# Alimentation.net
KiCad netlist of a schematic drawn in EAGLE
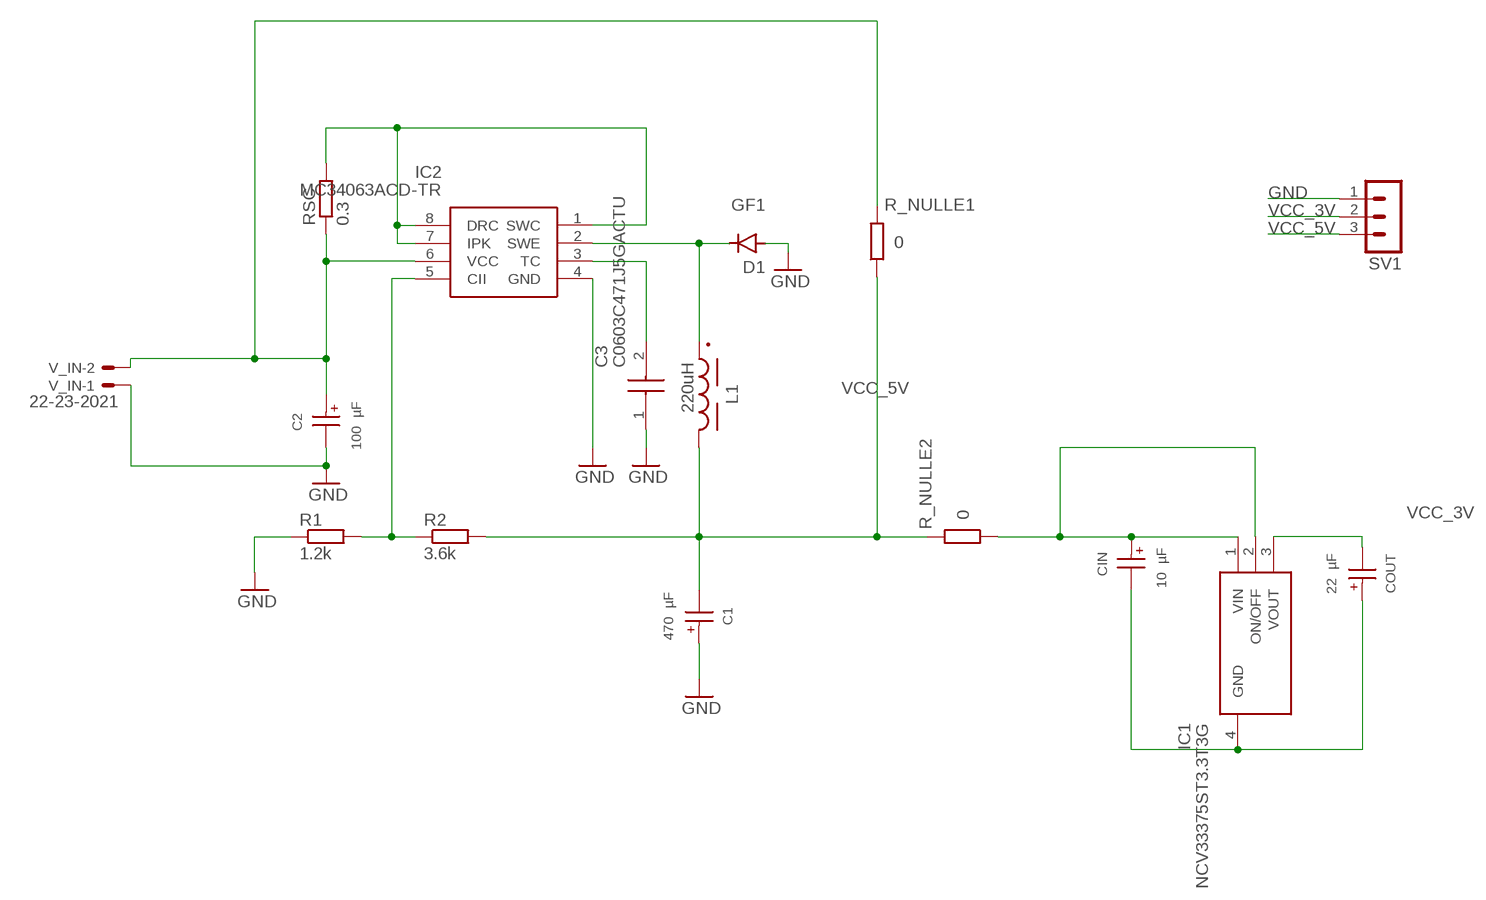
[diagram p0: schematic, sheet 1]

(export (version "E")
  (design (tool "Eeschema 10.0.6"))
  (components
    (comp (ref "C1")
      (value "470 µF")
      (footprint "eagle-import:WCAP-ASLL_8X10.5(DXL)")
      (libsource (lib "eagle-import") (part "WCAP-ASLL_8X10.5_865060353009"))
    )
    (comp (ref "C2")
      (value "100 µF")
      (footprint "eagle-import:WCAP-ASLL_6.3X7.7(DXL)")
      (libsource (lib "eagle-import") (part "WCAP-ASLL_6.3X7.7_865060445005"))
    )
    (comp (ref "C3")
      (value "C0603C471J5GACTU")
      (footprint "eagle-import:C0603")
      (fields (field (name "MOUSER_PART_NUMBER") "80-C0603C471J5G"))
      (libsource (lib "eagle-import") (part "C0603C471J5GACTU"))
    )
    (comp (ref "CIN")
      (value "10 µF")
      (footprint "eagle-import:WCAP-ASLL_4X5.5(DXL)")
      (libsource (lib "eagle-import") (part "WCAP-ASLL_4X5.5_865060440001"))
    )
    (comp (ref "COUT")
      (value "22 µF")
      (footprint "eagle-import:WCAP-ASLL_5X5.5(DXL)")
      (libsource (lib "eagle-import") (part "WCAP-ASLL_5X5.5_865060442002"))
    )
    (comp (ref "D1")
      (value "GF1")
      (footprint "eagle-import:SMA-DO214AC")
      (libsource (lib "eagle-import") (part "GF1"))
    )
    (comp (ref "IC1")
      (value "NCV33375ST3.3T3G")
      (footprint "eagle-import:SOT230P700X175-4N")
      (fields (field (name "MOUSER_PART_NUMBER") "863-NCV33375ST3.3T3G"))
      (libsource (lib "eagle-import") (part "NCV33375ST3.3T3G"))
    )
    (comp (ref "IC2")
      (value "MC34063ACD-TR")
      (footprint "eagle-import:SOIC127P600X175-8N")
      (fields (field (name "MOUSER_PART_NUMBER") "511-MC34063ACD-TR"))
      (libsource (lib "eagle-import") (part "MC34063ACD-TR"))
    )
    (comp (ref "L1")
      (value "220uH")
      (footprint "eagle-import:WE-PDA_1260")
      (libsource (lib "eagle-import") (part "WE-PDA_1260_784771221"))
    )
    (comp (ref "R1")
      (value "1.2k")
      (footprint "eagle-import:R0603")
      (libsource (lib "eagle-import") (part "R-EU_R0603"))
    )
    (comp (ref "R2")
      (value "3.6k")
      (footprint "eagle-import:R0603")
      (libsource (lib "eagle-import") (part "R-EU_R0603"))
    )
    (comp (ref "RSC")
      (value "0.3")
      (footprint "eagle-import:R1206W")
      (libsource (lib "eagle-import") (part "R-EU_R1206W"))
    )
    (comp (ref "R_NULLE1")
      (value "0")
      (footprint "eagle-import:R0603")
      (libsource (lib "eagle-import") (part "R-EU_R0603"))
    )
    (comp (ref "R_NULLE2")
      (value "0")
      (footprint "eagle-import:R0603")
      (libsource (lib "eagle-import") (part "R-EU_R0603"))
    )
    (comp (ref "SV1")
      (value "MA03-1")
      (footprint "eagle-import:MA03-1")
      (libsource (lib "eagle-import") (part "MA03-1"))
    )
    (comp (ref "V_IN")
      (value "22-23-2021")
      (footprint "eagle-import:22-23-2021")
      (fields (field (name "MF") "MOLEX"))
      (libsource (lib "eagle-import") (part "22-23-2021"))
    )
  )
  (nets
    (net (code "1") (name "/VCC_3V") (class "Default")
      (node (ref "COUT") (pin "2") (pinfunction "-_2") (pintype "passive"))
      (node (ref "IC1") (pin "3") (pinfunction "VOUT_3") (pintype "bidirectional"))
      (node (ref "SV1") (pin "2") (pinfunction "2_2") (pintype "passive"))
    )
    (net (code "2") (name "/VCC_5V") (class "Default")
      (node (ref "C1") (pin "2") (pinfunction "-_2") (pintype "passive"))
      (node (ref "L1") (pin "2") (pinfunction "2_2") (pintype "passive"))
      (node (ref "R2") (pin "2") (pinfunction "2_2") (pintype "passive"))
      (node (ref "R_NULLE1") (pin "1") (pinfunction "1_1") (pintype "passive"))
      (node (ref "R_NULLE2") (pin "2") (pinfunction "2_2") (pintype "passive"))
      (node (ref "SV1") (pin "3") (pinfunction "3_3") (pintype "passive"))
    )
    (net (code "3") (name "GND") (class "Default")
      (node (ref "C1") (pin "1") (pinfunction "+_1") (pintype "passive"))
      (node (ref "C2") (pin "2") (pinfunction "-_2") (pintype "passive"))
      (node (ref "C3") (pin "1") (pinfunction "1_1") (pintype "bidirectional"))
      (node (ref "CIN") (pin "2") (pinfunction "-_2") (pintype "passive"))
      (node (ref "COUT") (pin "1") (pinfunction "+_1") (pintype "passive"))
      (node (ref "D1") (pin "A") (pinfunction "A_A") (pintype "passive"))
      (node (ref "IC1") (pin "4") (pinfunction "GND_4") (pintype "bidirectional"))
      (node (ref "IC2") (pin "4") (pinfunction "GND_4") (pintype "bidirectional"))
      (node (ref "R1") (pin "1") (pinfunction "1_1") (pintype "passive"))
      (node (ref "SV1") (pin "1") (pinfunction "1_1") (pintype "passive"))
      (node (ref "V_IN") (pin "1") (pinfunction "S_1") (pintype "passive"))
    )
    (net (code "4") (name "Net-(C2-+)") (class "Default")
      (node (ref "C2") (pin "1") (pinfunction "+_1") (pintype "passive"))
      (node (ref "IC2") (pin "6") (pinfunction "VCC_6") (pintype "bidirectional"))
      (node (ref "RSC") (pin "1") (pinfunction "1_1") (pintype "passive"))
      (node (ref "R_NULLE1") (pin "2") (pinfunction "2_2") (pintype "passive"))
      (node (ref "V_IN") (pin "2") (pinfunction "S_2") (pintype "passive"))
    )
    (net (code "5") (name "Net-(CIN-+)") (class "Default")
      (node (ref "CIN") (pin "1") (pinfunction "+_1") (pintype "passive"))
      (node (ref "IC1") (pin "1") (pinfunction "VIN_1") (pintype "bidirectional"))
      (node (ref "IC1") (pin "2") (pinfunction "ON/OFF_2") (pintype "bidirectional"))
      (node (ref "R_NULLE2") (pin "1") (pinfunction "1_1") (pintype "passive"))
    )
    (net (code "6") (name "Net-(D1-C)") (class "Default")
      (node (ref "D1") (pin "K") (pinfunction "C_K") (pintype "passive"))
      (node (ref "IC2") (pin "2") (pinfunction "SWE_2") (pintype "bidirectional"))
      (node (ref "L1") (pin "1") (pinfunction "1_1") (pintype "passive"))
    )
    (net (code "7") (name "Net-(IC2-CII)") (class "Default")
      (node (ref "IC2") (pin "5") (pinfunction "CII_5") (pintype "bidirectional"))
      (node (ref "R1") (pin "2") (pinfunction "2_2") (pintype "passive"))
      (node (ref "R2") (pin "1") (pinfunction "1_1") (pintype "passive"))
    )
    (net (code "8") (name "Net-(IC2-DRC)") (class "Default")
      (node (ref "IC2") (pin "1") (pinfunction "SWC_1") (pintype "bidirectional"))
      (node (ref "IC2") (pin "7") (pinfunction "IPK_7") (pintype "bidirectional"))
      (node (ref "IC2") (pin "8") (pinfunction "DRC_8") (pintype "bidirectional"))
      (node (ref "RSC") (pin "2") (pinfunction "2_2") (pintype "passive"))
    )
    (net (code "9") (name "Net-(IC2-TC)") (class "Default")
      (node (ref "C3") (pin "2") (pinfunction "2_2") (pintype "bidirectional"))
      (node (ref "IC2") (pin "3") (pinfunction "TC_3") (pintype "bidirectional"))
    )
  )
)
